# VU_Meter.net
KiCad netlist of a schematic drawn in EAGLE
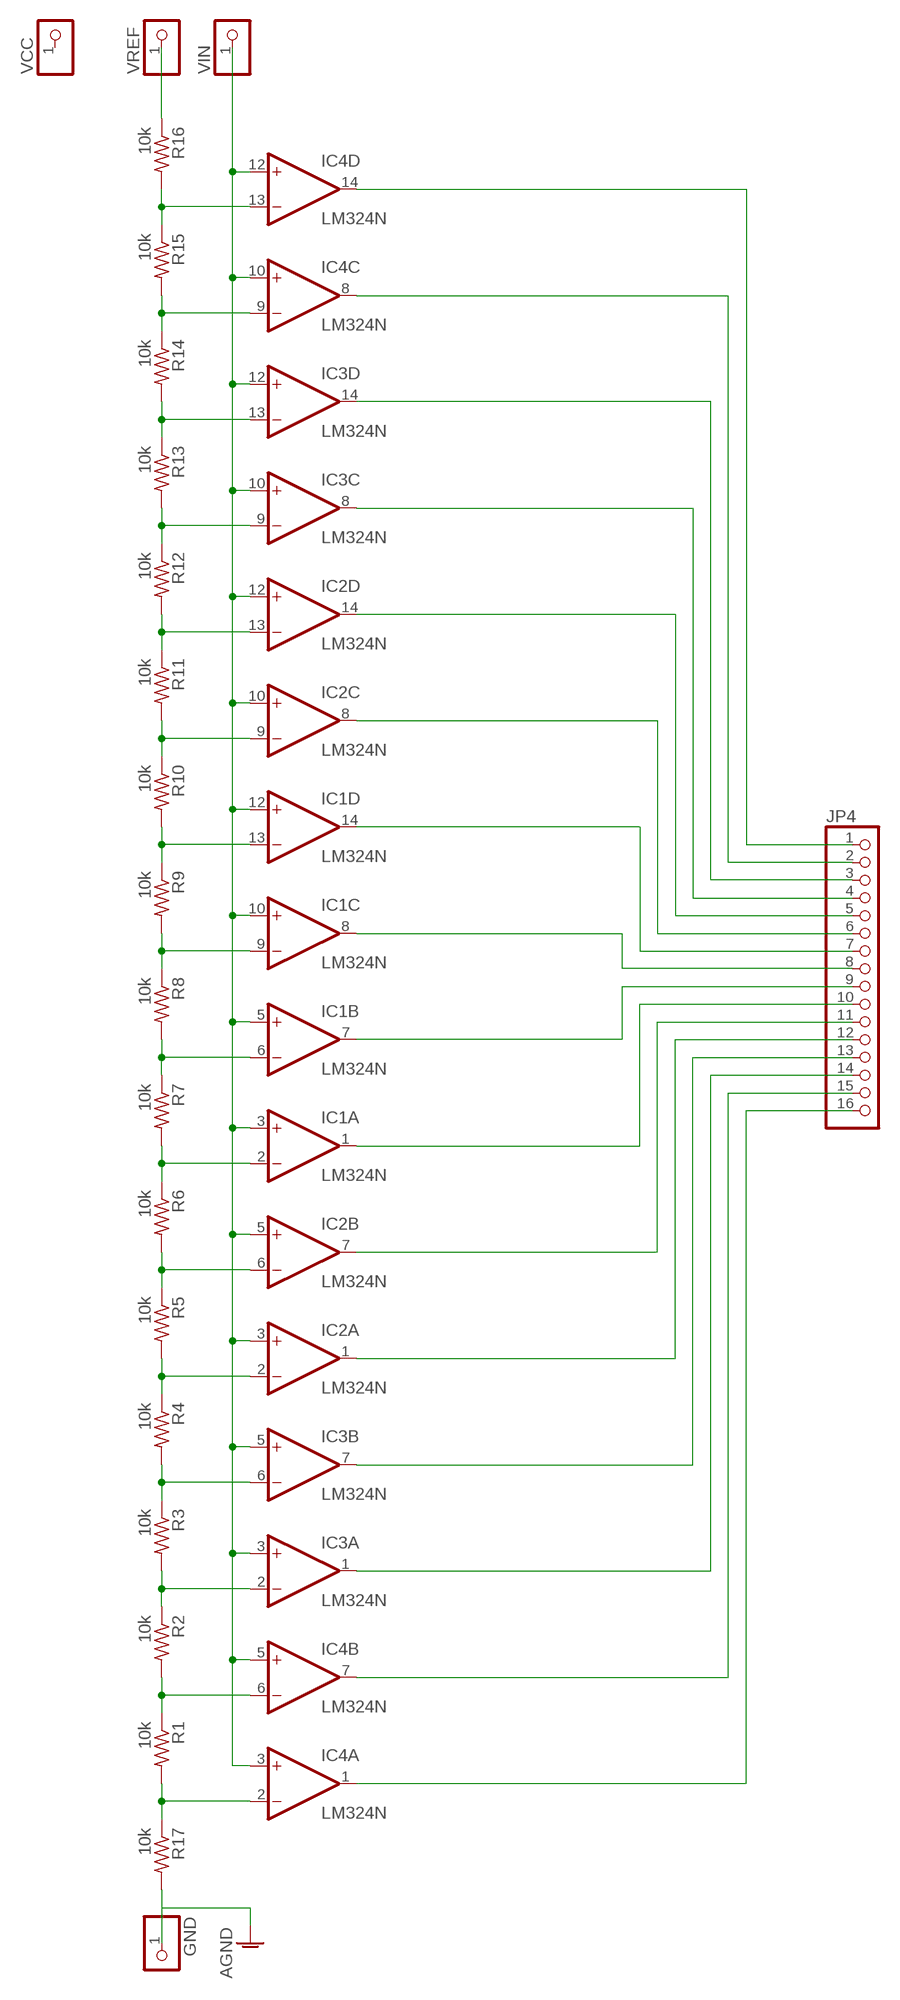
[diagram p0: schematic, sheet 1]

(export (version "E")
  (design (tool "Eeschema 10.0.6"))
  (components
    (comp (ref "GND")
      (value "PINHD-1X1")
      (footprint "eagle-import:1X01")
      (libsource (lib "eagle-import") (part "PINHD-1X1"))
    )
    (comp (ref "IC1")
      (value "LM324N")
      (footprint "eagle-import:DIL14")
      (libsource (lib "eagle-import") (part "LM324N"))
    )
    (comp (ref "IC2")
      (value "LM324N")
      (footprint "eagle-import:DIL14")
      (libsource (lib "eagle-import") (part "LM324N"))
    )
    (comp (ref "IC3")
      (value "LM324N")
      (footprint "eagle-import:DIL14")
      (libsource (lib "eagle-import") (part "LM324N"))
    )
    (comp (ref "IC4")
      (value "LM324N")
      (footprint "eagle-import:DIL14")
      (libsource (lib "eagle-import") (part "LM324N"))
    )
    (comp (ref "JP4")
      (value "PINHD-1X16")
      (footprint "eagle-import:1X16")
      (libsource (lib "eagle-import") (part "PINHD-1X16"))
    )
    (comp (ref "R1")
      (value "10k")
      (footprint "eagle-import:0204_7")
      (libsource (lib "eagle-import") (part "R-US_0204/7"))
    )
    (comp (ref "R2")
      (value "10k")
      (footprint "eagle-import:0204_7")
      (libsource (lib "eagle-import") (part "R-US_0204/7"))
    )
    (comp (ref "R3")
      (value "10k")
      (footprint "eagle-import:0204_7")
      (libsource (lib "eagle-import") (part "R-US_0204/7"))
    )
    (comp (ref "R4")
      (value "10k")
      (footprint "eagle-import:0204_7")
      (libsource (lib "eagle-import") (part "R-US_0204/7"))
    )
    (comp (ref "R5")
      (value "10k")
      (footprint "eagle-import:0204_7")
      (libsource (lib "eagle-import") (part "R-US_0204/7"))
    )
    (comp (ref "R6")
      (value "10k")
      (footprint "eagle-import:0204_7")
      (libsource (lib "eagle-import") (part "R-US_0204/7"))
    )
    (comp (ref "R7")
      (value "10k")
      (footprint "eagle-import:0204_7")
      (libsource (lib "eagle-import") (part "R-US_0204/7"))
    )
    (comp (ref "R8")
      (value "10k")
      (footprint "eagle-import:0204_7")
      (libsource (lib "eagle-import") (part "R-US_0204/7"))
    )
    (comp (ref "R9")
      (value "10k")
      (footprint "eagle-import:0204_7")
      (libsource (lib "eagle-import") (part "R-US_0204/7"))
    )
    (comp (ref "R10")
      (value "10k")
      (footprint "eagle-import:0204_7")
      (libsource (lib "eagle-import") (part "R-US_0204/7"))
    )
    (comp (ref "R11")
      (value "10k")
      (footprint "eagle-import:0204_7")
      (libsource (lib "eagle-import") (part "R-US_0204/7"))
    )
    (comp (ref "R12")
      (value "10k")
      (footprint "eagle-import:0204_7")
      (libsource (lib "eagle-import") (part "R-US_0204/7"))
    )
    (comp (ref "R13")
      (value "10k")
      (footprint "eagle-import:0204_7")
      (libsource (lib "eagle-import") (part "R-US_0204/7"))
    )
    (comp (ref "R14")
      (value "10k")
      (footprint "eagle-import:0204_7")
      (libsource (lib "eagle-import") (part "R-US_0204/7"))
    )
    (comp (ref "R15")
      (value "10k")
      (footprint "eagle-import:0204_7")
      (libsource (lib "eagle-import") (part "R-US_0204/7"))
    )
    (comp (ref "R16")
      (value "10k")
      (footprint "eagle-import:0204_7")
      (libsource (lib "eagle-import") (part "R-US_0204/7"))
    )
    (comp (ref "R17")
      (value "10k")
      (footprint "eagle-import:0204_7")
      (libsource (lib "eagle-import") (part "R-US_0204/7"))
    )
    (comp (ref "VCC")
      (value "PINHD-1X1")
      (footprint "eagle-import:1X01")
      (libsource (lib "eagle-import") (part "PINHD-1X1"))
    )
    (comp (ref "VIN")
      (value "PINHD-1X1")
      (footprint "eagle-import:1X01")
      (libsource (lib "eagle-import") (part "PINHD-1X1"))
    )
    (comp (ref "VREF")
      (value "PINHD-1X1")
      (footprint "eagle-import:1X01")
      (libsource (lib "eagle-import") (part "PINHD-1X1"))
    )
  )
  (nets
    (net (code "1") (name "AGND") (class "Default")
      (node (ref "GND") (pin "1") (pinfunction "1_1") (pintype "passive"))
      (node (ref "R17") (pin "2") (pinfunction "2_2") (pintype "passive"))
    )
    (net (code "2") (name "Net-(IC1A-+IN)") (class "Default")
      (node (ref "IC1") (pin "10") (pinfunction "+IN_10") (pintype "input"))
      (node (ref "IC1") (pin "12") (pinfunction "+IN_12") (pintype "input"))
      (node (ref "IC1") (pin "3") (pinfunction "+IN_3") (pintype "input"))
      (node (ref "IC1") (pin "5") (pinfunction "+IN_5") (pintype "input"))
      (node (ref "IC2") (pin "10") (pinfunction "+IN_10") (pintype "input"))
      (node (ref "IC2") (pin "12") (pinfunction "+IN_12") (pintype "input"))
      (node (ref "IC2") (pin "3") (pinfunction "+IN_3") (pintype "input"))
      (node (ref "IC2") (pin "5") (pinfunction "+IN_5") (pintype "input"))
      (node (ref "IC3") (pin "10") (pinfunction "+IN_10") (pintype "input"))
      (node (ref "IC3") (pin "12") (pinfunction "+IN_12") (pintype "input"))
      (node (ref "IC3") (pin "3") (pinfunction "+IN_3") (pintype "input"))
      (node (ref "IC3") (pin "5") (pinfunction "+IN_5") (pintype "input"))
      (node (ref "IC4") (pin "10") (pinfunction "+IN_10") (pintype "input"))
      (node (ref "IC4") (pin "12") (pinfunction "+IN_12") (pintype "input"))
      (node (ref "IC4") (pin "3") (pinfunction "+IN_3") (pintype "input"))
      (node (ref "IC4") (pin "5") (pinfunction "+IN_5") (pintype "input"))
      (node (ref "VIN") (pin "1") (pinfunction "1_1") (pintype "passive"))
    )
    (net (code "3") (name "Net-(IC1A--IN)") (class "Default")
      (node (ref "IC1") (pin "2") (pinfunction "-IN_2") (pintype "input"))
      (node (ref "R6") (pin "1") (pinfunction "1_1") (pintype "passive"))
      (node (ref "R7") (pin "2") (pinfunction "2_2") (pintype "passive"))
    )
    (net (code "4") (name "Net-(IC1A-OUT)") (class "Default")
      (node (ref "IC1") (pin "1") (pinfunction "OUT_1") (pintype "output"))
      (node (ref "JP4") (pin "10") (pinfunction "10_10") (pintype "passive"))
    )
    (net (code "5") (name "Net-(IC1B--IN)") (class "Default")
      (node (ref "IC1") (pin "6") (pinfunction "-IN_6") (pintype "input"))
      (node (ref "R7") (pin "1") (pinfunction "1_1") (pintype "passive"))
      (node (ref "R8") (pin "2") (pinfunction "2_2") (pintype "passive"))
    )
    (net (code "6") (name "Net-(IC1B-OUT)") (class "Default")
      (node (ref "IC1") (pin "7") (pinfunction "OUT_7") (pintype "output"))
      (node (ref "JP4") (pin "9") (pinfunction "9_9") (pintype "passive"))
    )
    (net (code "7") (name "Net-(IC1C--IN)") (class "Default")
      (node (ref "IC1") (pin "9") (pinfunction "-IN_9") (pintype "input"))
      (node (ref "R8") (pin "1") (pinfunction "1_1") (pintype "passive"))
      (node (ref "R9") (pin "2") (pinfunction "2_2") (pintype "passive"))
    )
    (net (code "8") (name "Net-(IC1C-OUT)") (class "Default")
      (node (ref "IC1") (pin "8") (pinfunction "OUT_8") (pintype "output"))
      (node (ref "JP4") (pin "8") (pinfunction "8_8") (pintype "passive"))
    )
    (net (code "9") (name "Net-(IC1D--IN)") (class "Default")
      (node (ref "IC1") (pin "13") (pinfunction "-IN_13") (pintype "input"))
      (node (ref "R10") (pin "2") (pinfunction "2_2") (pintype "passive"))
      (node (ref "R9") (pin "1") (pinfunction "1_1") (pintype "passive"))
    )
    (net (code "10") (name "Net-(IC1D-OUT)") (class "Default")
      (node (ref "IC1") (pin "14") (pinfunction "OUT_14") (pintype "output"))
      (node (ref "JP4") (pin "7") (pinfunction "7_7") (pintype "passive"))
    )
    (net (code "11") (name "Net-(IC2A--IN)") (class "Default")
      (node (ref "IC2") (pin "2") (pinfunction "-IN_2") (pintype "input"))
      (node (ref "R4") (pin "1") (pinfunction "1_1") (pintype "passive"))
      (node (ref "R5") (pin "2") (pinfunction "2_2") (pintype "passive"))
    )
    (net (code "12") (name "Net-(IC2A-OUT)") (class "Default")
      (node (ref "IC2") (pin "1") (pinfunction "OUT_1") (pintype "output"))
      (node (ref "JP4") (pin "12") (pinfunction "12_12") (pintype "passive"))
    )
    (net (code "13") (name "Net-(IC2B--IN)") (class "Default")
      (node (ref "IC2") (pin "6") (pinfunction "-IN_6") (pintype "input"))
      (node (ref "R5") (pin "1") (pinfunction "1_1") (pintype "passive"))
      (node (ref "R6") (pin "2") (pinfunction "2_2") (pintype "passive"))
    )
    (net (code "14") (name "Net-(IC2B-OUT)") (class "Default")
      (node (ref "IC2") (pin "7") (pinfunction "OUT_7") (pintype "output"))
      (node (ref "JP4") (pin "11") (pinfunction "11_11") (pintype "passive"))
    )
    (net (code "15") (name "Net-(IC2C--IN)") (class "Default")
      (node (ref "IC2") (pin "9") (pinfunction "-IN_9") (pintype "input"))
      (node (ref "R10") (pin "1") (pinfunction "1_1") (pintype "passive"))
      (node (ref "R11") (pin "2") (pinfunction "2_2") (pintype "passive"))
    )
    (net (code "16") (name "Net-(IC2C-OUT)") (class "Default")
      (node (ref "IC2") (pin "8") (pinfunction "OUT_8") (pintype "output"))
      (node (ref "JP4") (pin "6") (pinfunction "6_6") (pintype "passive"))
    )
    (net (code "17") (name "Net-(IC2D--IN)") (class "Default")
      (node (ref "IC2") (pin "13") (pinfunction "-IN_13") (pintype "input"))
      (node (ref "R11") (pin "1") (pinfunction "1_1") (pintype "passive"))
      (node (ref "R12") (pin "2") (pinfunction "2_2") (pintype "passive"))
    )
    (net (code "18") (name "Net-(IC2D-OUT)") (class "Default")
      (node (ref "IC2") (pin "14") (pinfunction "OUT_14") (pintype "output"))
      (node (ref "JP4") (pin "5") (pinfunction "5_5") (pintype "passive"))
    )
    (net (code "19") (name "Net-(IC3A--IN)") (class "Default")
      (node (ref "IC3") (pin "2") (pinfunction "-IN_2") (pintype "input"))
      (node (ref "R2") (pin "1") (pinfunction "1_1") (pintype "passive"))
      (node (ref "R3") (pin "2") (pinfunction "2_2") (pintype "passive"))
    )
    (net (code "20") (name "Net-(IC3A-OUT)") (class "Default")
      (node (ref "IC3") (pin "1") (pinfunction "OUT_1") (pintype "output"))
      (node (ref "JP4") (pin "14") (pinfunction "14_14") (pintype "passive"))
    )
    (net (code "21") (name "Net-(IC3B--IN)") (class "Default")
      (node (ref "IC3") (pin "6") (pinfunction "-IN_6") (pintype "input"))
      (node (ref "R3") (pin "1") (pinfunction "1_1") (pintype "passive"))
      (node (ref "R4") (pin "2") (pinfunction "2_2") (pintype "passive"))
    )
    (net (code "22") (name "Net-(IC3B-OUT)") (class "Default")
      (node (ref "IC3") (pin "7") (pinfunction "OUT_7") (pintype "output"))
      (node (ref "JP4") (pin "13") (pinfunction "13_13") (pintype "passive"))
    )
    (net (code "23") (name "Net-(IC3C--IN)") (class "Default")
      (node (ref "IC3") (pin "9") (pinfunction "-IN_9") (pintype "input"))
      (node (ref "R12") (pin "1") (pinfunction "1_1") (pintype "passive"))
      (node (ref "R13") (pin "2") (pinfunction "2_2") (pintype "passive"))
    )
    (net (code "24") (name "Net-(IC3C-OUT)") (class "Default")
      (node (ref "IC3") (pin "8") (pinfunction "OUT_8") (pintype "output"))
      (node (ref "JP4") (pin "4") (pinfunction "4_4") (pintype "passive"))
    )
    (net (code "25") (name "Net-(IC3D--IN)") (class "Default")
      (node (ref "IC3") (pin "13") (pinfunction "-IN_13") (pintype "input"))
      (node (ref "R13") (pin "1") (pinfunction "1_1") (pintype "passive"))
      (node (ref "R14") (pin "2") (pinfunction "2_2") (pintype "passive"))
    )
    (net (code "26") (name "Net-(IC3D-OUT)") (class "Default")
      (node (ref "IC3") (pin "14") (pinfunction "OUT_14") (pintype "output"))
      (node (ref "JP4") (pin "3") (pinfunction "3_3") (pintype "passive"))
    )
    (net (code "27") (name "Net-(IC4A--IN)") (class "Default")
      (node (ref "IC4") (pin "2") (pinfunction "-IN_2") (pintype "input"))
      (node (ref "R1") (pin "2") (pinfunction "2_2") (pintype "passive"))
      (node (ref "R17") (pin "1") (pinfunction "1_1") (pintype "passive"))
    )
    (net (code "28") (name "Net-(IC4A-OUT)") (class "Default")
      (node (ref "IC4") (pin "1") (pinfunction "OUT_1") (pintype "output"))
      (node (ref "JP4") (pin "16") (pinfunction "16_16") (pintype "passive"))
    )
    (net (code "29") (name "Net-(IC4B--IN)") (class "Default")
      (node (ref "IC4") (pin "6") (pinfunction "-IN_6") (pintype "input"))
      (node (ref "R1") (pin "1") (pinfunction "1_1") (pintype "passive"))
      (node (ref "R2") (pin "2") (pinfunction "2_2") (pintype "passive"))
    )
    (net (code "30") (name "Net-(IC4B-OUT)") (class "Default")
      (node (ref "IC4") (pin "7") (pinfunction "OUT_7") (pintype "output"))
      (node (ref "JP4") (pin "15") (pinfunction "15_15") (pintype "passive"))
    )
    (net (code "31") (name "Net-(IC4C--IN)") (class "Default")
      (node (ref "IC4") (pin "9") (pinfunction "-IN_9") (pintype "input"))
      (node (ref "R14") (pin "1") (pinfunction "1_1") (pintype "passive"))
      (node (ref "R15") (pin "2") (pinfunction "2_2") (pintype "passive"))
    )
    (net (code "32") (name "Net-(IC4C-OUT)") (class "Default")
      (node (ref "IC4") (pin "8") (pinfunction "OUT_8") (pintype "output"))
      (node (ref "JP4") (pin "2") (pinfunction "2_2") (pintype "passive"))
    )
    (net (code "33") (name "Net-(IC4D--IN)") (class "Default")
      (node (ref "IC4") (pin "13") (pinfunction "-IN_13") (pintype "input"))
      (node (ref "R15") (pin "1") (pinfunction "1_1") (pintype "passive"))
      (node (ref "R16") (pin "2") (pinfunction "2_2") (pintype "passive"))
    )
    (net (code "34") (name "Net-(IC4D-OUT)") (class "Default")
      (node (ref "IC4") (pin "14") (pinfunction "OUT_14") (pintype "output"))
      (node (ref "JP4") (pin "1") (pinfunction "1_1") (pintype "passive"))
    )
    (net (code "35") (name "Net-(R16-Pad1)") (class "Default")
      (node (ref "R16") (pin "1") (pinfunction "1_1") (pintype "passive"))
      (node (ref "VREF") (pin "1") (pinfunction "1_1") (pintype "passive"))
    )
    (net (code "36") (name "unconnected-(VCC-Pad1)") (class "Default")
      (node (ref "VCC") (pin "1") (pinfunction "1_1") (pintype "passive"))
    )
  )
)
